# LaundryMote.net
KiCad netlist of a schematic drawn in EAGLE
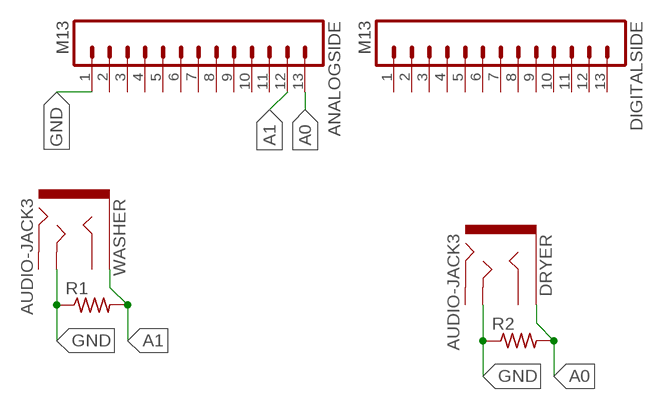
[diagram p0: schematic, sheet 1]

(export (version "E")
  (design (tool "Eeschema 10.0.6"))
  (components
    (comp (ref "ANALOGSIDE")
      (value "M13")
      (footprint "eagle-import:1X13")
      (libsource (lib "eagle-import") (part "M13"))
    )
    (comp (ref "DIGITALSIDE")
      (value "M13")
      (footprint "eagle-import:1X13")
      (libsource (lib "eagle-import") (part "M13"))
    )
    (comp (ref "DRYER")
      (value "AUDIO-JACK3")
      (footprint "eagle-import:AUDIO-JACK-TRRS-SMD")
      (libsource (lib "eagle-import") (part "AUDIO-JACK3"))
    )
    (comp (ref "R1")
      (value "R-US_0207/7")
      (footprint "eagle-import:0207_7")
      (libsource (lib "eagle-import") (part "R-US_0207/7"))
    )
    (comp (ref "R2")
      (value "R-US_0207/7")
      (footprint "eagle-import:0207_7")
      (libsource (lib "eagle-import") (part "R-US_0207/7"))
    )
    (comp (ref "WASHER")
      (value "AUDIO-JACK3")
      (footprint "eagle-import:AUDIO-JACK-TRRS-SMD")
      (libsource (lib "eagle-import") (part "AUDIO-JACK3"))
    )
  )
  (nets
    (net (code "1") (name "A0") (class "Default")
      (node (ref "ANALOGSIDE") (pin "13") (pinfunction "13_13") (pintype "passive"))
      (node (ref "DRYER") (pin "EARTH") (pinfunction "EARTH_EARTH") (pintype "bidirectional"))
      (node (ref "R2") (pin "2") (pinfunction "2_2") (pintype "passive"))
    )
    (net (code "2") (name "A1") (class "Default")
      (node (ref "ANALOGSIDE") (pin "12") (pinfunction "12_12") (pintype "passive"))
      (node (ref "R1") (pin "2") (pinfunction "2_2") (pintype "passive"))
      (node (ref "WASHER") (pin "EARTH") (pinfunction "EARTH_EARTH") (pintype "bidirectional"))
    )
    (net (code "3") (name "GND") (class "Default")
      (node (ref "ANALOGSIDE") (pin "1") (pinfunction "1_1") (pintype "passive"))
      (node (ref "DRYER") (pin "TIP") (pinfunction "TIP_TIP") (pintype "bidirectional"))
      (node (ref "R1") (pin "1") (pinfunction "1_1") (pintype "passive"))
      (node (ref "R2") (pin "1") (pinfunction "1_1") (pintype "passive"))
      (node (ref "WASHER") (pin "TIP") (pinfunction "TIP_TIP") (pintype "bidirectional"))
    )
    (net (code "4") (name "unconnected-(ANALOGSIDE-Pad2)") (class "Default")
      (node (ref "ANALOGSIDE") (pin "2") (pinfunction "2_2") (pintype "passive"))
    )
    (net (code "5") (name "unconnected-(ANALOGSIDE-Pad3)") (class "Default")
      (node (ref "ANALOGSIDE") (pin "3") (pinfunction "3_3") (pintype "passive"))
    )
    (net (code "6") (name "unconnected-(ANALOGSIDE-Pad4)") (class "Default")
      (node (ref "ANALOGSIDE") (pin "4") (pinfunction "4_4") (pintype "passive"))
    )
    (net (code "7") (name "unconnected-(ANALOGSIDE-Pad5)") (class "Default")
      (node (ref "ANALOGSIDE") (pin "5") (pinfunction "5_5") (pintype "passive"))
    )
    (net (code "8") (name "unconnected-(ANALOGSIDE-Pad6)") (class "Default")
      (node (ref "ANALOGSIDE") (pin "6") (pinfunction "6_6") (pintype "passive"))
    )
    (net (code "9") (name "unconnected-(ANALOGSIDE-Pad7)") (class "Default")
      (node (ref "ANALOGSIDE") (pin "7") (pinfunction "7_7") (pintype "passive"))
    )
    (net (code "10") (name "unconnected-(ANALOGSIDE-Pad8)") (class "Default")
      (node (ref "ANALOGSIDE") (pin "8") (pinfunction "8_8") (pintype "passive"))
    )
    (net (code "11") (name "unconnected-(ANALOGSIDE-Pad9)") (class "Default")
      (node (ref "ANALOGSIDE") (pin "9") (pinfunction "9_9") (pintype "passive"))
    )
    (net (code "12") (name "unconnected-(ANALOGSIDE-Pad10)") (class "Default")
      (node (ref "ANALOGSIDE") (pin "10") (pinfunction "10_10") (pintype "passive"))
    )
    (net (code "13") (name "unconnected-(ANALOGSIDE-Pad11)") (class "Default")
      (node (ref "ANALOGSIDE") (pin "11") (pinfunction "11_11") (pintype "passive"))
    )
    (net (code "14") (name "unconnected-(DIGITALSIDE-Pad1)") (class "Default")
      (node (ref "DIGITALSIDE") (pin "1") (pinfunction "1_1") (pintype "passive"))
    )
    (net (code "15") (name "unconnected-(DIGITALSIDE-Pad2)") (class "Default")
      (node (ref "DIGITALSIDE") (pin "2") (pinfunction "2_2") (pintype "passive"))
    )
    (net (code "16") (name "unconnected-(DIGITALSIDE-Pad3)") (class "Default")
      (node (ref "DIGITALSIDE") (pin "3") (pinfunction "3_3") (pintype "passive"))
    )
    (net (code "17") (name "unconnected-(DIGITALSIDE-Pad4)") (class "Default")
      (node (ref "DIGITALSIDE") (pin "4") (pinfunction "4_4") (pintype "passive"))
    )
    (net (code "18") (name "unconnected-(DIGITALSIDE-Pad5)") (class "Default")
      (node (ref "DIGITALSIDE") (pin "5") (pinfunction "5_5") (pintype "passive"))
    )
    (net (code "19") (name "unconnected-(DIGITALSIDE-Pad6)") (class "Default")
      (node (ref "DIGITALSIDE") (pin "6") (pinfunction "6_6") (pintype "passive"))
    )
    (net (code "20") (name "unconnected-(DIGITALSIDE-Pad7)") (class "Default")
      (node (ref "DIGITALSIDE") (pin "7") (pinfunction "7_7") (pintype "passive"))
    )
    (net (code "21") (name "unconnected-(DIGITALSIDE-Pad8)") (class "Default")
      (node (ref "DIGITALSIDE") (pin "8") (pinfunction "8_8") (pintype "passive"))
    )
    (net (code "22") (name "unconnected-(DIGITALSIDE-Pad9)") (class "Default")
      (node (ref "DIGITALSIDE") (pin "9") (pinfunction "9_9") (pintype "passive"))
    )
    (net (code "23") (name "unconnected-(DIGITALSIDE-Pad10)") (class "Default")
      (node (ref "DIGITALSIDE") (pin "10") (pinfunction "10_10") (pintype "passive"))
    )
    (net (code "24") (name "unconnected-(DIGITALSIDE-Pad11)") (class "Default")
      (node (ref "DIGITALSIDE") (pin "11") (pinfunction "11_11") (pintype "passive"))
    )
    (net (code "25") (name "unconnected-(DIGITALSIDE-Pad12)") (class "Default")
      (node (ref "DIGITALSIDE") (pin "12") (pinfunction "12_12") (pintype "passive"))
    )
    (net (code "26") (name "unconnected-(DIGITALSIDE-Pad13)") (class "Default")
      (node (ref "DIGITALSIDE") (pin "13") (pinfunction "13_13") (pintype "passive"))
    )
    (net (code "27") (name "unconnected-(DRYER-PadRING1)") (class "Default")
      (node (ref "DRYER") (pin "RING1") (pinfunction "RING1_RING1") (pintype "bidirectional"))
    )
    (net (code "28") (name "unconnected-(DRYER-PadRING2)") (class "Default")
      (node (ref "DRYER") (pin "RING2") (pinfunction "RING2_RING2") (pintype "bidirectional"))
    )
    (net (code "29") (name "unconnected-(WASHER-PadRING1)") (class "Default")
      (node (ref "WASHER") (pin "RING1") (pinfunction "RING1_RING1") (pintype "bidirectional"))
    )
    (net (code "30") (name "unconnected-(WASHER-PadRING2)") (class "Default")
      (node (ref "WASHER") (pin "RING2") (pinfunction "RING2_RING2") (pintype "bidirectional"))
    )
  )
)
